# esquema.net
KiCad netlist of a schematic drawn in EAGLE
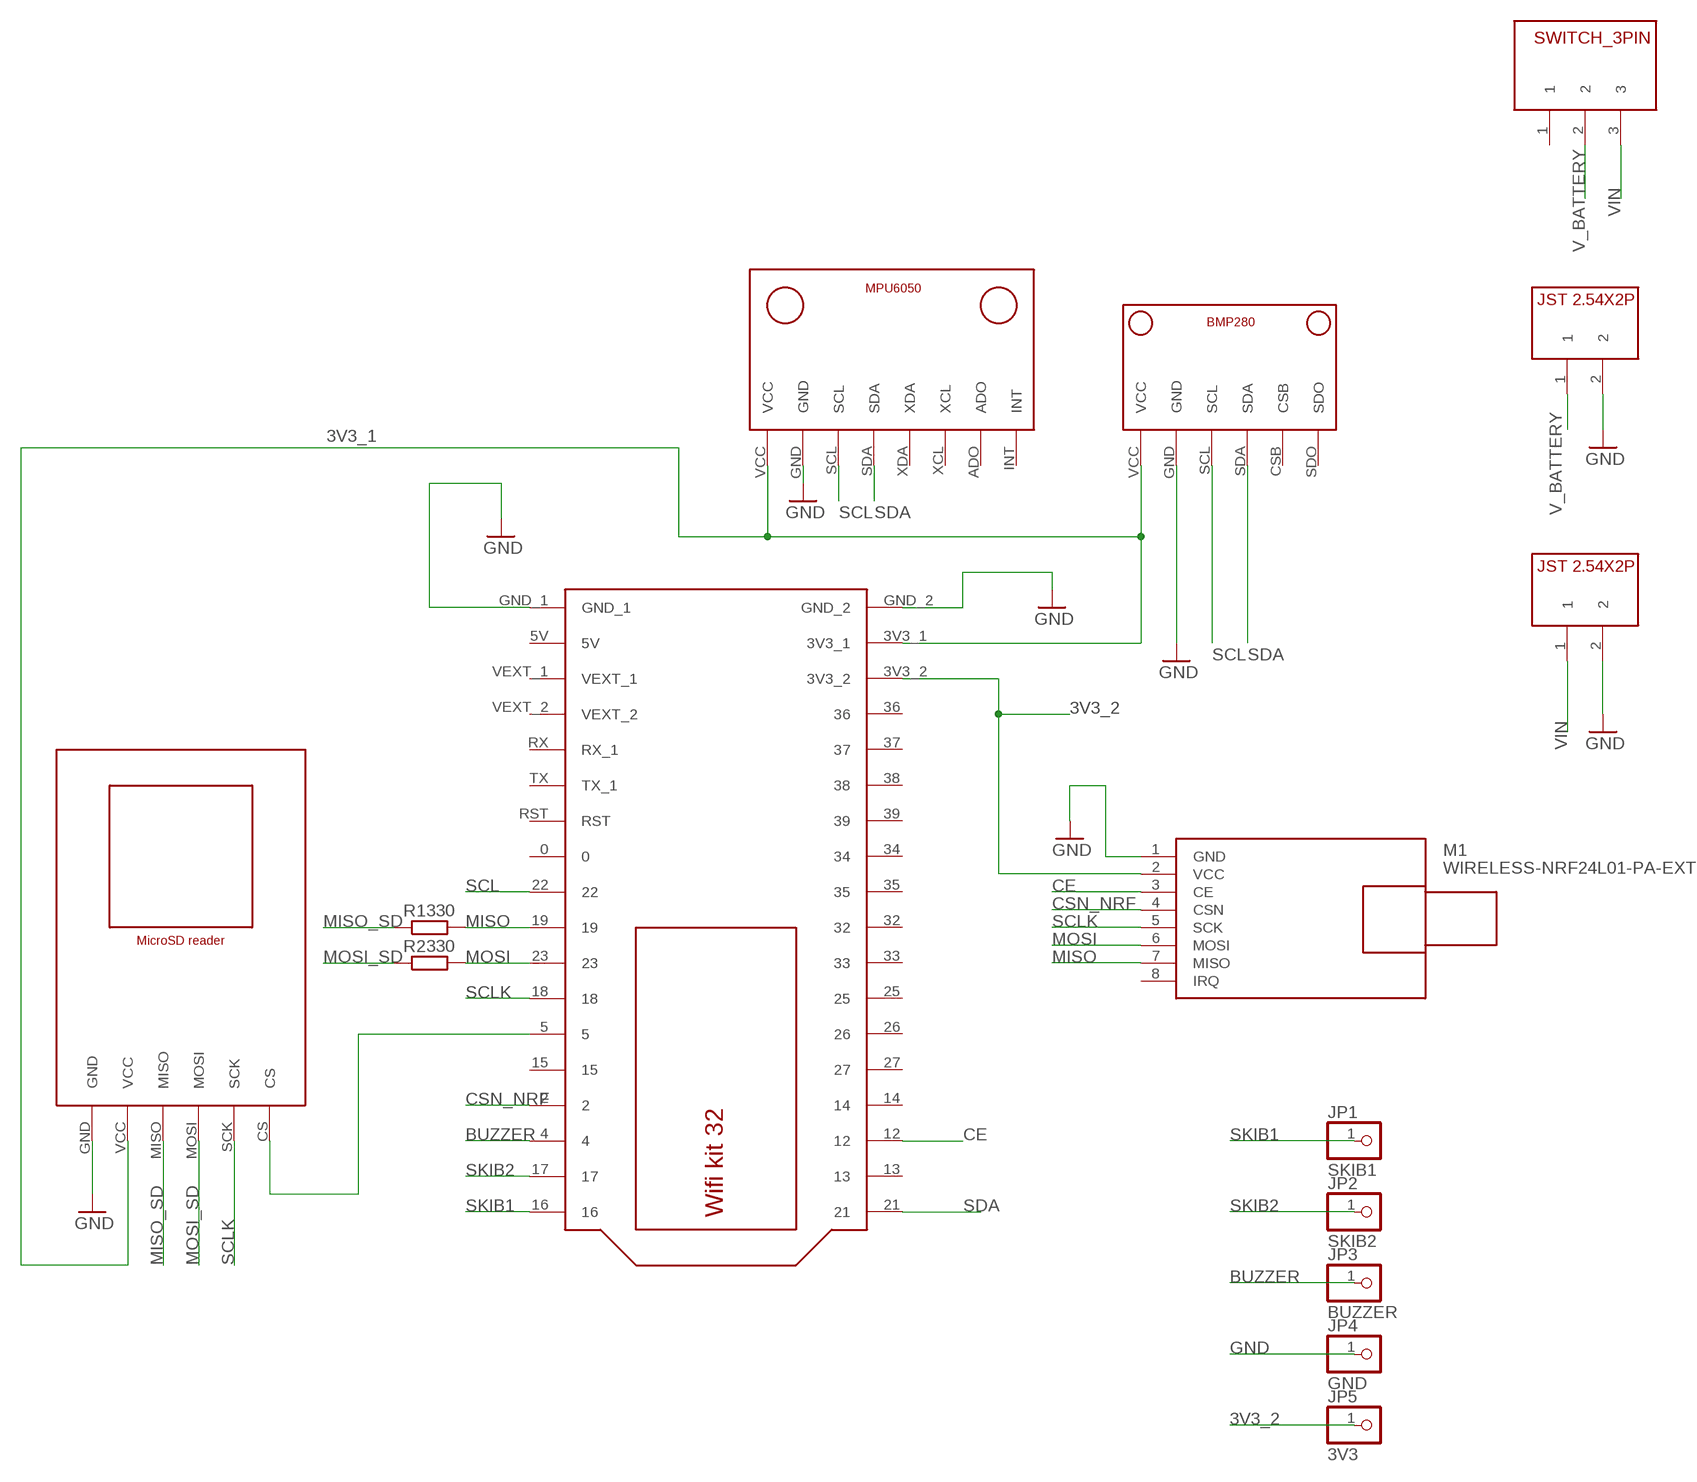
[diagram p0: schematic, sheet 1]

(export (version "E")
  (design (tool "Eeschema 10.0.6"))
  (components
    (comp (ref "JP1")
      (value "SKIB1")
      (footprint "eagle-import:1X01")
      (libsource (lib "eagle-import") (part "PINHD-1X1"))
    )
    (comp (ref "JP2")
      (value "SKIB2")
      (footprint "eagle-import:1X01")
      (libsource (lib "eagle-import") (part "PINHD-1X1"))
    )
    (comp (ref "JP3")
      (value "BUZZER")
      (footprint "eagle-import:1X01")
      (libsource (lib "eagle-import") (part "PINHD-1X1"))
    )
    (comp (ref "JP4")
      (value "GND")
      (footprint "eagle-import:1X01")
      (libsource (lib "eagle-import") (part "PINHD-1X1"))
    )
    (comp (ref "JP5")
      (value "3V3")
      (footprint "eagle-import:1X01")
      (libsource (lib "eagle-import") (part "PINHD-1X1"))
    )
    (comp (ref "M1")
      (value "WIRELESS-NRF24L01-PA-EXT")
      (footprint "eagle-import:WIRELESS-NRF24L01-PA-EXT")
      (libsource (lib "eagle-import") (part "WIRELESS-NRF24L01-PA-EXT"))
    )
    (comp (ref "R1")
      (value "330")
      (footprint "eagle-import:0207_10")
      (libsource (lib "eagle-import") (part "R-EU_0207/10"))
    )
    (comp (ref "R2")
      (value "330")
      (footprint "eagle-import:0207_10")
      (libsource (lib "eagle-import") (part "R-EU_0207/10"))
    )
    (comp (ref "U$1")
      (value "BMP280V1")
      (footprint "eagle-import:BMP280_FOOTPRINT")
      (libsource (lib "eagle-import") (part "BMP280V1"))
    )
    (comp (ref "U$2")
      (value "MICROSD_READER")
      (footprint "eagle-import:MICROSD_READER_FOOTPRINT")
      (libsource (lib "eagle-import") (part "MICROSD_READER"))
    )
    (comp (ref "U$3")
      (value "MPU6050V1")
      (footprint "eagle-import:MPU6050_FOOTPRINT")
      (libsource (lib "eagle-import") (part "MPU6050V1"))
    )
    (comp (ref "U$4")
      (value "WIFI_KIT32")
      (footprint "eagle-import:WIFI_KIT32")
      (libsource (lib "eagle-import") (part "WIFI_KIT32"))
    )
    (comp (ref "U$5")
      (value "JST2.54X2P")
      (footprint "eagle-import:JST2.54X2P_FOOTPRINT")
      (libsource (lib "eagle-import") (part "JST2.54X2P"))
    )
    (comp (ref "U$6")
      (value "SWITCH_3PIN")
      (footprint "eagle-import:SWITCH_3PIN")
      (libsource (lib "eagle-import") (part "SWITCH_3PIN"))
    )
    (comp (ref "U$7")
      (value "JST2.54X2P")
      (footprint "eagle-import:JST2.54X2P_FOOTPRINT")
      (libsource (lib "eagle-import") (part "JST2.54X2P"))
    )
  )
  (nets
    (net (code "1") (name "/3V3_1") (class "Default")
      (node (ref "U$1") (pin "VCC") (pinfunction "VCC_VCC") (pintype "bidirectional"))
      (node (ref "U$2") (pin "VCC") (pinfunction "VCC_VCC") (pintype "bidirectional"))
      (node (ref "U$3") (pin "VCC") (pinfunction "VCC_VCC") (pintype "bidirectional"))
      (node (ref "U$4") (pin "3V3_1") (pinfunction "3V3_1_3V3_1") (pintype "bidirectional"))
    )
    (net (code "2") (name "/3V3_2") (class "Default")
      (node (ref "JP5") (pin "1") (pinfunction "1_1") (pintype "passive"))
      (node (ref "M1") (pin "2") (pinfunction "VCC_2") (pintype "power_in"))
      (node (ref "U$4") (pin "3V3_2") (pinfunction "3V3_2_3V3_2") (pintype "bidirectional"))
    )
    (net (code "3") (name "/BUZZER") (class "Default")
      (node (ref "JP3") (pin "1") (pinfunction "1_1") (pintype "passive"))
      (node (ref "U$4") (pin "4") (pinfunction "4_4") (pintype "bidirectional"))
    )
    (net (code "4") (name "/CE") (class "Default")
      (node (ref "M1") (pin "3") (pinfunction "CE_3") (pintype "bidirectional"))
      (node (ref "U$4") (pin "12") (pinfunction "12_12") (pintype "bidirectional"))
    )
    (net (code "5") (name "/CSN_NRF") (class "Default")
      (node (ref "M1") (pin "4") (pinfunction "CSN_4") (pintype "bidirectional"))
      (node (ref "U$4") (pin "2") (pinfunction "2_2") (pintype "bidirectional"))
    )
    (net (code "6") (name "/MISO") (class "Default")
      (node (ref "M1") (pin "7") (pinfunction "MISO_7") (pintype "bidirectional"))
      (node (ref "R1") (pin "2") (pinfunction "2_2") (pintype "passive"))
      (node (ref "U$4") (pin "19") (pinfunction "19_19") (pintype "bidirectional"))
    )
    (net (code "7") (name "/MISO_SD") (class "Default")
      (node (ref "R1") (pin "1") (pinfunction "1_1") (pintype "passive"))
      (node (ref "U$2") (pin "MISO") (pinfunction "MISO_MISO") (pintype "bidirectional"))
    )
    (net (code "8") (name "/MOSI") (class "Default")
      (node (ref "M1") (pin "6") (pinfunction "MOSI_6") (pintype "bidirectional"))
      (node (ref "R2") (pin "2") (pinfunction "2_2") (pintype "passive"))
      (node (ref "U$4") (pin "23") (pinfunction "23_23") (pintype "bidirectional"))
    )
    (net (code "9") (name "/MOSI_SD") (class "Default")
      (node (ref "R2") (pin "1") (pinfunction "1_1") (pintype "passive"))
      (node (ref "U$2") (pin "MOSI") (pinfunction "MOSI_MOSI") (pintype "bidirectional"))
    )
    (net (code "10") (name "/SCL") (class "Default")
      (node (ref "U$1") (pin "SCL") (pinfunction "SCL_SCL") (pintype "bidirectional"))
      (node (ref "U$3") (pin "SCL") (pinfunction "SCL_SCL") (pintype "bidirectional"))
      (node (ref "U$4") (pin "22") (pinfunction "22_22") (pintype "bidirectional"))
    )
    (net (code "11") (name "/SCLK") (class "Default")
      (node (ref "M1") (pin "5") (pinfunction "SCK_5") (pintype "bidirectional"))
      (node (ref "U$2") (pin "SCK") (pinfunction "SCK_SCK") (pintype "bidirectional"))
      (node (ref "U$4") (pin "18") (pinfunction "18_18") (pintype "bidirectional"))
    )
    (net (code "12") (name "/SDA") (class "Default")
      (node (ref "U$1") (pin "SDA") (pinfunction "SDA_SDA") (pintype "bidirectional"))
      (node (ref "U$3") (pin "SDA") (pinfunction "SDA_SDA") (pintype "bidirectional"))
      (node (ref "U$4") (pin "21") (pinfunction "21_21") (pintype "bidirectional"))
    )
    (net (code "13") (name "/SKIB1") (class "Default")
      (node (ref "JP1") (pin "1") (pinfunction "1_1") (pintype "passive"))
      (node (ref "U$4") (pin "16") (pinfunction "16_16") (pintype "bidirectional"))
    )
    (net (code "14") (name "/SKIB2") (class "Default")
      (node (ref "JP2") (pin "1") (pinfunction "1_1") (pintype "passive"))
      (node (ref "U$4") (pin "17") (pinfunction "17_17") (pintype "bidirectional"))
    )
    (net (code "15") (name "/VIN") (class "Default")
      (node (ref "U$6") (pin "3") (pinfunction "3_3") (pintype "bidirectional"))
      (node (ref "U$7") (pin "1") (pinfunction "1_1") (pintype "bidirectional"))
    )
    (net (code "16") (name "/V_BATTERY") (class "Default")
      (node (ref "U$5") (pin "1") (pinfunction "1_1") (pintype "bidirectional"))
      (node (ref "U$6") (pin "2") (pinfunction "2_2") (pintype "bidirectional"))
    )
    (net (code "17") (name "GND") (class "Default")
      (node (ref "JP4") (pin "1") (pinfunction "1_1") (pintype "passive"))
      (node (ref "M1") (pin "1") (pinfunction "GND_1") (pintype "power_in"))
      (node (ref "U$1") (pin "GND") (pinfunction "GND_GND") (pintype "bidirectional"))
      (node (ref "U$2") (pin "GND") (pinfunction "GND_GND") (pintype "bidirectional"))
      (node (ref "U$3") (pin "GND") (pinfunction "GND_GND") (pintype "bidirectional"))
      (node (ref "U$4") (pin "GND_1") (pinfunction "GND_1_GND_1") (pintype "bidirectional"))
      (node (ref "U$4") (pin "GND_2") (pinfunction "GND_2_GND_2") (pintype "bidirectional"))
      (node (ref "U$5") (pin "2") (pinfunction "2_2") (pintype "bidirectional"))
      (node (ref "U$7") (pin "2") (pinfunction "2_2") (pintype "bidirectional"))
    )
    (net (code "18") (name "Net-(U$2-PadCS)") (class "Default")
      (node (ref "U$2") (pin "CS") (pinfunction "CS_CS") (pintype "bidirectional"))
      (node (ref "U$4") (pin "5") (pinfunction "5_5") (pintype "bidirectional"))
    )
    (net (code "19") (name "unconnected-(M1-IRQ-Pad8)") (class "Default")
      (node (ref "M1") (pin "8") (pinfunction "IRQ_8") (pintype "bidirectional"))
    )
    (net (code "20") (name "unconnected-(U$1-PadCSB)") (class "Default")
      (node (ref "U$1") (pin "CSB") (pinfunction "CSB_CSB") (pintype "bidirectional"))
    )
    (net (code "21") (name "unconnected-(U$1-PadSDO)") (class "Default")
      (node (ref "U$1") (pin "SDO") (pinfunction "SDO_SDO") (pintype "bidirectional"))
    )
    (net (code "22") (name "unconnected-(U$3-PadADO)") (class "Default")
      (node (ref "U$3") (pin "ADO") (pinfunction "ADO_ADO") (pintype "bidirectional"))
    )
    (net (code "23") (name "unconnected-(U$3-PadINT)") (class "Default")
      (node (ref "U$3") (pin "INT") (pinfunction "INT_INT") (pintype "bidirectional"))
    )
    (net (code "24") (name "unconnected-(U$3-PadXCL)") (class "Default")
      (node (ref "U$3") (pin "XCL") (pinfunction "XCL_XCL") (pintype "bidirectional"))
    )
    (net (code "25") (name "unconnected-(U$3-PadXDA)") (class "Default")
      (node (ref "U$3") (pin "XDA") (pinfunction "XDA_XDA") (pintype "bidirectional"))
    )
    (net (code "26") (name "unconnected-(U$4-Pad0)") (class "Default")
      (node (ref "U$4") (pin "0") (pinfunction "0_0") (pintype "bidirectional"))
    )
    (net (code "27") (name "unconnected-(U$4-Pad5V)") (class "Default")
      (node (ref "U$4") (pin "5V") (pinfunction "5V_5V") (pintype "bidirectional"))
    )
    (net (code "28") (name "unconnected-(U$4-Pad13)") (class "Default")
      (node (ref "U$4") (pin "13") (pinfunction "13_13") (pintype "bidirectional"))
    )
    (net (code "29") (name "unconnected-(U$4-Pad14)") (class "Default")
      (node (ref "U$4") (pin "14") (pinfunction "14_14") (pintype "bidirectional"))
    )
    (net (code "30") (name "unconnected-(U$4-Pad15)") (class "Default")
      (node (ref "U$4") (pin "15") (pinfunction "15_15") (pintype "bidirectional"))
    )
    (net (code "31") (name "unconnected-(U$4-Pad25)") (class "Default")
      (node (ref "U$4") (pin "25") (pinfunction "25_25") (pintype "bidirectional"))
    )
    (net (code "32") (name "unconnected-(U$4-Pad26)") (class "Default")
      (node (ref "U$4") (pin "26") (pinfunction "26_26") (pintype "bidirectional"))
    )
    (net (code "33") (name "unconnected-(U$4-Pad27)") (class "Default")
      (node (ref "U$4") (pin "27") (pinfunction "27_27") (pintype "bidirectional"))
    )
    (net (code "34") (name "unconnected-(U$4-Pad32)") (class "Default")
      (node (ref "U$4") (pin "32") (pinfunction "32_32") (pintype "bidirectional"))
    )
    (net (code "35") (name "unconnected-(U$4-Pad33)") (class "Default")
      (node (ref "U$4") (pin "33") (pinfunction "33_33") (pintype "bidirectional"))
    )
    (net (code "36") (name "unconnected-(U$4-Pad34)") (class "Default")
      (node (ref "U$4") (pin "34") (pinfunction "34_34") (pintype "bidirectional"))
    )
    (net (code "37") (name "unconnected-(U$4-Pad35)") (class "Default")
      (node (ref "U$4") (pin "35") (pinfunction "35_35") (pintype "bidirectional"))
    )
    (net (code "38") (name "unconnected-(U$4-Pad36)") (class "Default")
      (node (ref "U$4") (pin "36") (pinfunction "36_36") (pintype "bidirectional"))
    )
    (net (code "39") (name "unconnected-(U$4-Pad37)") (class "Default")
      (node (ref "U$4") (pin "37") (pinfunction "37_37") (pintype "bidirectional"))
    )
    (net (code "40") (name "unconnected-(U$4-Pad38)") (class "Default")
      (node (ref "U$4") (pin "38") (pinfunction "38_38") (pintype "bidirectional"))
    )
    (net (code "41") (name "unconnected-(U$4-Pad39)") (class "Default")
      (node (ref "U$4") (pin "39") (pinfunction "39_39") (pintype "bidirectional"))
    )
    (net (code "42") (name "unconnected-(U$4-PadRST)") (class "Default")
      (node (ref "U$4") (pin "RST") (pinfunction "RST_RST") (pintype "bidirectional"))
    )
    (net (code "43") (name "unconnected-(U$4-PadVEXT_1)") (class "Default")
      (node (ref "U$4") (pin "VEXT_1") (pinfunction "VEXT_1_VEXT_1") (pintype "bidirectional"))
    )
    (net (code "44") (name "unconnected-(U$4-PadVEXT_2)") (class "Default")
      (node (ref "U$4") (pin "VEXT_2") (pinfunction "VEXT_2_VEXT_2") (pintype "bidirectional"))
    )
    (net (code "45") (name "unconnected-(U$4-RX_1-PadRX)") (class "Default")
      (node (ref "U$4") (pin "RX") (pinfunction "RX_1_RX") (pintype "bidirectional"))
    )
    (net (code "46") (name "unconnected-(U$4-TX_1-PadTX)") (class "Default")
      (node (ref "U$4") (pin "TX") (pinfunction "TX_1_TX") (pintype "bidirectional"))
    )
    (net (code "47") (name "unconnected-(U$6-Pad1)") (class "Default")
      (node (ref "U$6") (pin "1") (pinfunction "1_1") (pintype "bidirectional"))
    )
  )
)
